# Display.net
KiCad netlist of a schematic drawn in Altium Designer
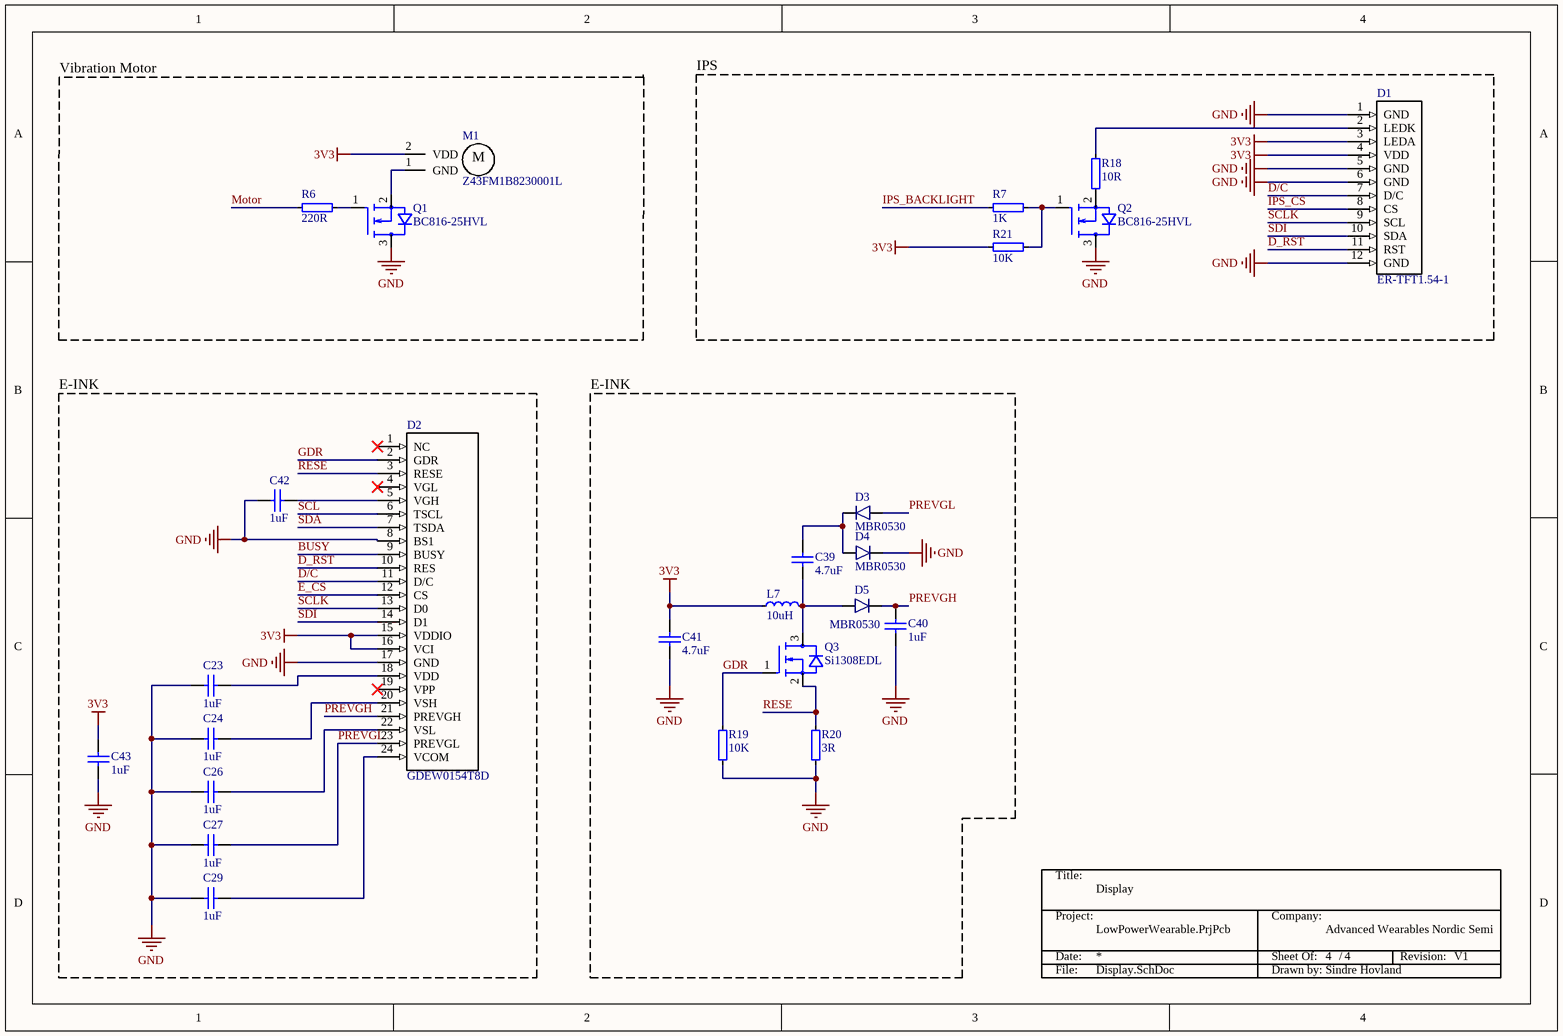
[diagram p0: Display.SchDoc]

(export (version "E")
  (design (tool "Eeschema 10.0.6"))
  (components
    (comp (ref "C23")
      (value "1uF")
      (footprint "C0402")
      (description "Capacitor")
      (fields (field (name "PUBLISHER") "Altium Limited"))
      (libsource (lib "Passives") (part "CAP"))
    )
    (comp (ref "C24")
      (value "1uF")
      (footprint "C0402")
      (description "Capacitor")
      (fields (field (name "PUBLISHER") "Altium Limited"))
      (libsource (lib "Passives") (part "CAP"))
    )
    (comp (ref "C26")
      (value "1uF")
      (footprint "C0402")
      (description "Capacitor")
      (fields (field (name "PUBLISHER") "Altium Limited"))
      (libsource (lib "Passives") (part "CAP"))
    )
    (comp (ref "C27")
      (value "1uF")
      (footprint "C0402")
      (description "Capacitor")
      (fields (field (name "PUBLISHER") "Altium Limited"))
      (libsource (lib "Passives") (part "CAP"))
    )
    (comp (ref "C29")
      (value "1uF")
      (footprint "C0402")
      (description "Capacitor")
      (fields (field (name "PUBLISHER") "Altium Limited"))
      (libsource (lib "Passives") (part "CAP"))
    )
    (comp (ref "C39")
      (value "4.7uF")
      (footprint "C0402")
      (description "Capacitor")
      (fields (field (name "PUBLISHER") "Altium Limited"))
      (libsource (lib "Passives") (part "CAP"))
    )
    (comp (ref "C40")
      (value "1uF")
      (footprint "C0402")
      (description "Capacitor")
      (fields (field (name "PUBLISHER") "Altium Limited"))
      (libsource (lib "Passives") (part "CAP"))
    )
    (comp (ref "C41")
      (value "4.7uF")
      (footprint "C0402")
      (description "Capacitor")
      (fields (field (name "PUBLISHER") "Altium Limited"))
      (libsource (lib "Passives") (part "CAP"))
    )
    (comp (ref "C42")
      (value "1uF")
      (footprint "C0402")
      (description "Capacitor")
      (fields (field (name "PUBLISHER") "Altium Limited"))
      (libsource (lib "Passives") (part "CAP"))
    )
    (comp (ref "C43")
      (value "1uF")
      (footprint "C0402")
      (description "Capacitor")
      (fields (field (name "PUBLISHER") "Altium Limited"))
      (libsource (lib "Passives") (part "CAP"))
    )
    (comp (ref "D1")
      (value "ER-TFT1.54-1")
      (footprint "IPS 1.54 inches")
      (description "IPS display 1.54 inch SPI")
      (libsource (lib "MISC") (part "IPS 1.54 inch"))
    )
    (comp (ref "D2")
      (value "GDEW0154T8D")
      (footprint "E-Papaer 1.54inches")
      (description "E-Paper 1.54 inch with integrated driver")
      (libsource (lib "MISC") (part "E-Paper 1.54 inch"))
    )
    (comp (ref "D3")
      (value "MBR0530")
      (footprint "SOD-123")
      (description "Switch-mode Schottky\r\nPower Rectifier\r\n250 V, 40 A")
      (libsource (lib "Passives") (part "Diode"))
    )
    (comp (ref "D4")
      (value "MBR0530")
      (footprint "SOD-123")
      (description "Switch-mode Schottky\r\nPower Rectifier\r\n250 V, 40 A")
      (libsource (lib "Passives") (part "Diode"))
    )
    (comp (ref "D5")
      (value "MBR0530")
      (footprint "SOD-123")
      (description "Switch-mode Schottky\r\nPower Rectifier\r\n250 V, 40 A")
      (libsource (lib "Passives") (part "Diode"))
    )
    (comp (ref "L7")
      (value "10uH")
      (footprint "IND0402")
      (description "Inductor")
      (fields
        (field (name "PART NUMBER") "FB0402-120R@100M-500mA")
        (field (name "MANUFACTURER") "Murata")
        (field (name "PUBLISHER") "Nordic Semiconductor")
      )
      (libsource (lib "Passives") (part "IND"))
    )
    (comp (ref "M1")
      (value "Z43FM1B8230001L")
      (footprint "Z43FM1B8230001L")
      (libsource (lib "MISC") (part "Vibration Motor"))
    )
    (comp (ref "Q1")
      (value "BC816-25HVL")
      (footprint "SOT23-3")
      (description "N-Channel 20V 100mA _Ta_ 150mW _Ta_ Surface Mount VMT3")
      (fields (field (name "MF") "Rohm") (field (name "DIGI-KEY_PART_NUMBER") "RUM001L02T2CLCT-ND"))
      (libsource (lib "") (part "Transistor_1"))
    )
    (comp (ref "Q2")
      (value "BC816-25HVL")
      (footprint "SOT23-3")
      (description "N-Channel 20V 100mA _Ta_ 150mW _Ta_ Surface Mount VMT3")
      (fields (field (name "MF") "Rohm") (field (name "DIGI-KEY_PART_NUMBER") "RUM001L02T2CLCT-ND"))
      (libsource (lib "") (part "Transistor_1"))
    )
    (comp (ref "Q3")
      (value "Si1308EDL")
      (footprint "SOT323")
      (description "N-Channel 20V 100mA _Ta_ 150mW _Ta_ Surface Mount VMT3")
      (fields (field (name "MF") "Rohm") (field (name "DIGI-KEY_PART_NUMBER") "RUM001L02T2CLCT-ND"))
      (libsource (lib "MCU") (part "Transistor"))
    )
    (comp (ref "R6")
      (value "220R")
      (footprint "RES0603R")
      (description "Resistor, ±5%, 0.05W")
      (fields (field (name "PART NUMBER") "R0201-0R") (field (name "PUBLISHER") "Nordic Semiconductor"))
      (libsource (lib "Passives") (part "RES"))
    )
    (comp (ref "R7")
      (value "1K")
      (footprint "RES0402")
      (description "Resistor, ±5%, 0.05W")
      (fields (field (name "PART NUMBER") "R0201-0R") (field (name "PUBLISHER") "Nordic Semiconductor"))
      (libsource (lib "Passives") (part "RES"))
    )
    (comp (ref "R18")
      (value "10R")
      (footprint "RES0402")
      (description "Resistor, ±5%, 0.05W")
      (fields (field (name "PART NUMBER") "R0201-0R") (field (name "PUBLISHER") "Nordic Semiconductor"))
      (libsource (lib "Passives") (part "RES"))
    )
    (comp (ref "R19")
      (value "10K")
      (footprint "RES0402")
      (description "Resistor, ±5%, 0.05W")
      (fields (field (name "PART NUMBER") "R0201-0R") (field (name "PUBLISHER") "Nordic Semiconductor"))
      (libsource (lib "Passives") (part "RES"))
    )
    (comp (ref "R20")
      (value "3R")
      (footprint "RES0402")
      (description "Resistor, ±5%, 0.05W")
      (fields (field (name "PART NUMBER") "R0201-0R") (field (name "PUBLISHER") "Nordic Semiconductor"))
      (libsource (lib "Passives") (part "RES"))
    )
    (comp (ref "R21")
      (value "10K")
      (footprint "RES0402")
      (description "Resistor, ±5%, 0.05W")
      (fields (field (name "PART NUMBER") "R0201-0R") (field (name "PUBLISHER") "Nordic Semiconductor"))
      (libsource (lib "Passives") (part "RES"))
    )
  )
  (nets
    (net (code "1") (name "/BUSY") (class "Default")
      (node (ref "D2") (pin "9") (pinfunction "BUSY_9") (pintype "input"))
    )
    (net (code "2") (name "/D_RST") (class "Default")
      (node (ref "D1") (pin "11") (pinfunction "RST_11") (pintype "input"))
      (node (ref "D2") (pin "10") (pinfunction "RES_10") (pintype "input"))
    )
    (net (code "3") (name "/D{slash}C") (class "Default")
      (node (ref "D1") (pin "7") (pinfunction "D/C_7") (pintype "input"))
      (node (ref "D2") (pin "11") (pinfunction "D/C_11") (pintype "input"))
    )
    (net (code "4") (name "/E_CS") (class "Default")
      (node (ref "D2") (pin "12") (pinfunction "CS_12") (pintype "input"))
    )
    (net (code "5") (name "/GDR") (class "Default")
      (node (ref "D2") (pin "2") (pinfunction "GDR_2") (pintype "input"))
      (node (ref "Q3") (pin "1") (pinfunction "G_1") (pintype "passive"))
      (node (ref "R19") (pin "2") (pinfunction "2_2") (pintype "passive"))
    )
    (net (code "6") (name "/IPS_BACKLIGHT") (class "Default")
      (node (ref "R7") (pin "1") (pinfunction "1_1") (pintype "passive"))
    )
    (net (code "7") (name "/IPS_CS") (class "Default")
      (node (ref "D1") (pin "8") (pinfunction "CS_8") (pintype "input"))
    )
    (net (code "8") (name "/Motor") (class "Default")
      (node (ref "R6") (pin "1") (pinfunction "1_1") (pintype "passive"))
    )
    (net (code "9") (name "/PREVGH") (class "Default")
      (node (ref "C40") (pin "1") (pinfunction "1_1") (pintype "passive"))
      (node (ref "D2") (pin "21") (pinfunction "PREVGH_21") (pintype "input"))
      (node (ref "D5") (pin "2") (pinfunction "C_2") (pintype "passive"))
    )
    (net (code "10") (name "/PREVGL") (class "Default")
      (node (ref "C27") (pin "1") (pinfunction "1_1") (pintype "passive"))
      (node (ref "D2") (pin "23") (pinfunction "PREVGL_23") (pintype "input"))
      (node (ref "D3") (pin "1") (pinfunction "A_1") (pintype "passive"))
    )
    (net (code "11") (name "/RESE") (class "Default")
      (node (ref "D2") (pin "3") (pinfunction "RESE_3") (pintype "input"))
      (node (ref "Q3") (pin "2") (pinfunction "S_2") (pintype "passive"))
      (node (ref "R20") (pin "2") (pinfunction "2_2") (pintype "passive"))
    )
    (net (code "12") (name "/SCL") (class "Default")
      (node (ref "D2") (pin "6") (pinfunction "TSCL_6") (pintype "input"))
    )
    (net (code "13") (name "/SCLK") (class "Default")
      (node (ref "D1") (pin "9") (pinfunction "SCL_9") (pintype "input"))
      (node (ref "D2") (pin "13") (pinfunction "D0_13") (pintype "input"))
    )
    (net (code "14") (name "/SDA") (class "Default")
      (node (ref "D2") (pin "7") (pinfunction "TSDA_7") (pintype "input"))
    )
    (net (code "15") (name "/SDI") (class "Default")
      (node (ref "D1") (pin "10") (pinfunction "SDA_10") (pintype "input"))
      (node (ref "D2") (pin "14") (pinfunction "D1_14") (pintype "input"))
    )
    (net (code "16") (name "3V3") (class "Default")
      (node (ref "C41") (pin "1") (pinfunction "1_1") (pintype "passive"))
      (node (ref "C43") (pin "1") (pinfunction "1_1") (pintype "passive"))
      (node (ref "D1") (pin "3") (pinfunction "LEDA_3") (pintype "input"))
      (node (ref "D1") (pin "4") (pinfunction "VDD_4") (pintype "input"))
      (node (ref "D2") (pin "15") (pinfunction "VDDIO_15") (pintype "input"))
      (node (ref "D2") (pin "16") (pinfunction "VCI_16") (pintype "input"))
      (node (ref "L7") (pin "1") (pinfunction "1_1") (pintype "passive"))
      (node (ref "M1") (pin "2") (pinfunction "VDD_2") (pintype "passive"))
      (node (ref "R21") (pin "1") (pinfunction "1_1") (pintype "passive"))
    )
    (net (code "17") (name "GND") (class "Default")
      (node (ref "C23") (pin "2") (pinfunction "2_2") (pintype "passive"))
      (node (ref "C24") (pin "2") (pinfunction "2_2") (pintype "passive"))
      (node (ref "C26") (pin "2") (pinfunction "2_2") (pintype "passive"))
      (node (ref "C27") (pin "2") (pinfunction "2_2") (pintype "passive"))
      (node (ref "C29") (pin "2") (pinfunction "2_2") (pintype "passive"))
      (node (ref "C40") (pin "2") (pinfunction "2_2") (pintype "passive"))
      (node (ref "C41") (pin "2") (pinfunction "2_2") (pintype "passive"))
      (node (ref "C42") (pin "1") (pinfunction "1_1") (pintype "passive"))
      (node (ref "C43") (pin "2") (pinfunction "2_2") (pintype "passive"))
      (node (ref "D1") (pin "1") (pinfunction "GND_1") (pintype "input"))
      (node (ref "D1") (pin "12") (pinfunction "GND_12") (pintype "input"))
      (node (ref "D1") (pin "5") (pinfunction "GND_5") (pintype "input"))
      (node (ref "D1") (pin "6") (pinfunction "GND_6") (pintype "input"))
      (node (ref "D2") (pin "17") (pinfunction "GND_17") (pintype "input"))
      (node (ref "D2") (pin "8") (pinfunction "BS1_8") (pintype "input"))
      (node (ref "D4") (pin "2") (pinfunction "C_2") (pintype "passive"))
      (node (ref "Q1") (pin "3") (pinfunction "D_3") (pintype "passive"))
      (node (ref "Q2") (pin "3") (pinfunction "D_3") (pintype "passive"))
      (node (ref "R19") (pin "1") (pinfunction "1_1") (pintype "passive"))
      (node (ref "R20") (pin "1") (pinfunction "1_1") (pintype "passive"))
    )
    (net (code "18") (name "Net-(D1-LEDK)") (class "Default")
      (node (ref "D1") (pin "2") (pinfunction "LEDK_2") (pintype "input"))
      (node (ref "R18") (pin "2") (pinfunction "2_2") (pintype "passive"))
    )
    (net (code "19") (name "Net-(D2-VCOM)") (class "Default")
      (node (ref "C29") (pin "1") (pinfunction "1_1") (pintype "passive"))
      (node (ref "D2") (pin "24") (pinfunction "VCOM_24") (pintype "input"))
    )
    (net (code "20") (name "Net-(D2-VDD)") (class "Default")
      (node (ref "C23") (pin "1") (pinfunction "1_1") (pintype "passive"))
      (node (ref "D2") (pin "18") (pinfunction "VDD_18") (pintype "input"))
    )
    (net (code "21") (name "Net-(D2-VGH)") (class "Default")
      (node (ref "C42") (pin "2") (pinfunction "2_2") (pintype "passive"))
      (node (ref "D2") (pin "5") (pinfunction "VGH_5") (pintype "input"))
    )
    (net (code "22") (name "Net-(D2-VSH)") (class "Default")
      (node (ref "C24") (pin "1") (pinfunction "1_1") (pintype "passive"))
      (node (ref "D2") (pin "20") (pinfunction "VSH_20") (pintype "input"))
    )
    (net (code "23") (name "Net-(D2-VSL)") (class "Default")
      (node (ref "C26") (pin "1") (pinfunction "1_1") (pintype "passive"))
      (node (ref "D2") (pin "22") (pinfunction "VSL_22") (pintype "input"))
    )
    (net (code "24") (name "Net-(D3-C)") (class "Default")
      (node (ref "C39") (pin "1") (pinfunction "1_1") (pintype "passive"))
      (node (ref "D3") (pin "2") (pinfunction "C_2") (pintype "passive"))
      (node (ref "D4") (pin "1") (pinfunction "A_1") (pintype "passive"))
    )
    (net (code "25") (name "Net-(D5-A)") (class "Default")
      (node (ref "C39") (pin "2") (pinfunction "2_2") (pintype "passive"))
      (node (ref "D5") (pin "1") (pinfunction "A_1") (pintype "passive"))
      (node (ref "L7") (pin "2") (pinfunction "2_2") (pintype "passive"))
      (node (ref "Q3") (pin "3") (pinfunction "D_3") (pintype "passive"))
    )
    (net (code "26") (name "Net-(M1-GND)") (class "Default")
      (node (ref "M1") (pin "1") (pinfunction "GND_1") (pintype "passive"))
      (node (ref "Q1") (pin "2") (pinfunction "S_2") (pintype "passive"))
    )
    (net (code "27") (name "Net-(Q1-G)") (class "Default")
      (node (ref "Q1") (pin "1") (pinfunction "G_1") (pintype "passive"))
      (node (ref "R6") (pin "2") (pinfunction "2_2") (pintype "passive"))
    )
    (net (code "28") (name "Net-(Q2-G)") (class "Default")
      (node (ref "Q2") (pin "1") (pinfunction "G_1") (pintype "passive"))
      (node (ref "R21") (pin "2") (pinfunction "2_2") (pintype "passive"))
      (node (ref "R7") (pin "2") (pinfunction "2_2") (pintype "passive"))
    )
    (net (code "29") (name "Net-(Q2-S)") (class "Default")
      (node (ref "Q2") (pin "2") (pinfunction "S_2") (pintype "passive"))
      (node (ref "R18") (pin "1") (pinfunction "1_1") (pintype "passive"))
    )
    (net (code "30") (name "unconnected-(D2-NC-Pad1)") (class "Default")
      (node (ref "D2") (pin "1") (pinfunction "NC_1") (pintype "input+no_connect"))
    )
    (net (code "31") (name "unconnected-(D2-VGL-Pad4)") (class "Default")
      (node (ref "D2") (pin "4") (pinfunction "VGL_4") (pintype "input+no_connect"))
    )
    (net (code "32") (name "unconnected-(D2-VPP-Pad19)") (class "Default")
      (node (ref "D2") (pin "19") (pinfunction "VPP_19") (pintype "input+no_connect"))
    )
  )
)
